# 07_Connectors_ESP32.net
KiCad netlist of a schematic drawn in Altium Designer
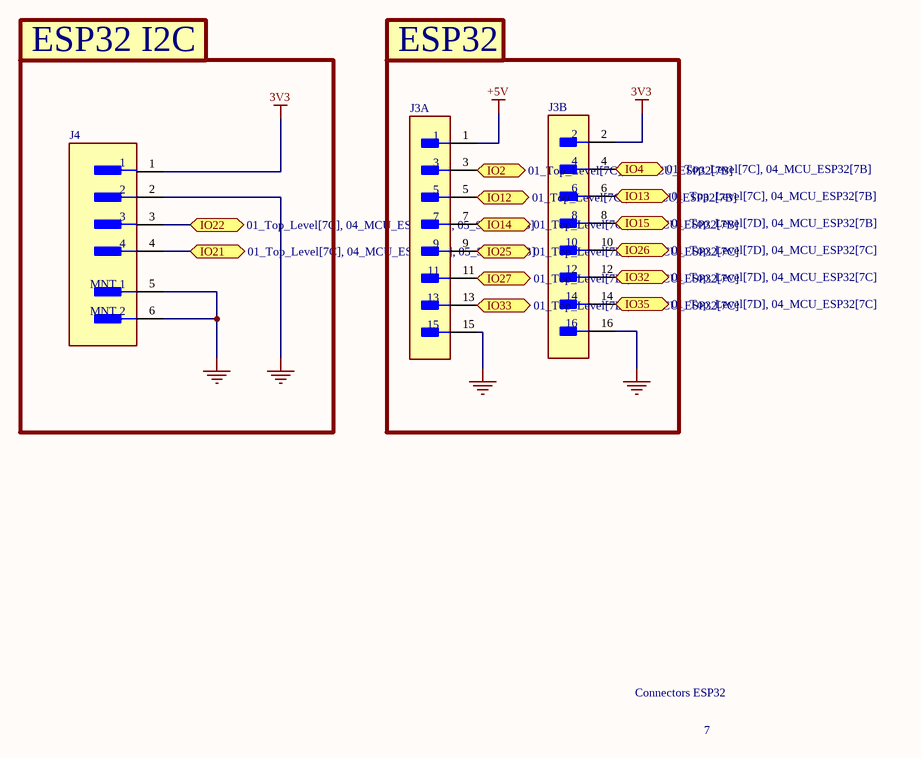
[diagram p0: 07_Connectors_ESP32.SchDoc]

(export (version "E")
  (design (tool "Eeschema 10.0.6"))
  (components
    (comp (ref "J3")
      (value "GRPB082MWCN-RC")
      (footprint "FP-GRPB082MWCN-RC-MFG")
      (description "CONN HEADER R/A 16POS 1.27MM")
      (libsource (lib "Altium Content Vault") (part "ecabc7128bd599dbeade09ffe984aba"))
    )
    (comp (ref "J4")
      (value "533980471")
      (footprint "FP-533980471-MFG")
      (description "Connector Header Surface Mount 4 position 0.049\" (1.25mm)")
      (fields (field (name "OCTOPART") "https://octopart.com/53398-0471-molex-655296"))
      (libsource (lib "Altium Content Vault") (part "3b6f738a5616415d78381ad43816e4a"))
    )
  )
  (nets
    (net (code "1") (name "+5V") (class "Default")
      (node (ref "J3") (pin "1") (pinfunction "1_1") (pintype "passive"))
    )
    (net (code "2") (name "/IO2") (class "Default")
      (node (ref "J3") (pin "3") (pinfunction "3_3") (pintype "passive"))
    )
    (net (code "3") (name "/IO4") (class "Default")
      (node (ref "J3") (pin "4") (pinfunction "4_4") (pintype "passive"))
    )
    (net (code "4") (name "/IO12") (class "Default")
      (node (ref "J3") (pin "5") (pinfunction "5_5") (pintype "passive"))
    )
    (net (code "5") (name "/IO13") (class "Default")
      (node (ref "J3") (pin "6") (pinfunction "6_6") (pintype "passive"))
    )
    (net (code "6") (name "/IO14") (class "Default")
      (node (ref "J3") (pin "7") (pinfunction "7_7") (pintype "passive"))
    )
    (net (code "7") (name "/IO15") (class "Default")
      (node (ref "J3") (pin "8") (pinfunction "8_8") (pintype "passive"))
    )
    (net (code "8") (name "/IO21") (class "Default")
      (node (ref "J4") (pin "4") (pinfunction "4_4") (pintype "passive"))
    )
    (net (code "9") (name "/IO22") (class "Default")
      (node (ref "J4") (pin "3") (pinfunction "3_3") (pintype "passive"))
    )
    (net (code "10") (name "/IO25") (class "Default")
      (node (ref "J3") (pin "9") (pinfunction "9_9") (pintype "passive"))
    )
    (net (code "11") (name "/IO26") (class "Default")
      (node (ref "J3") (pin "10") (pinfunction "10_10") (pintype "passive"))
    )
    (net (code "12") (name "/IO27") (class "Default")
      (node (ref "J3") (pin "11") (pinfunction "11_11") (pintype "passive"))
    )
    (net (code "13") (name "/IO32") (class "Default")
      (node (ref "J3") (pin "12") (pinfunction "12_12") (pintype "passive"))
    )
    (net (code "14") (name "/IO33") (class "Default")
      (node (ref "J3") (pin "13") (pinfunction "13_13") (pintype "passive"))
    )
    (net (code "15") (name "/IO35") (class "Default")
      (node (ref "J3") (pin "14") (pinfunction "14_14") (pintype "passive"))
    )
    (net (code "16") (name "3V3") (class "Default")
      (node (ref "J3") (pin "2") (pinfunction "2_2") (pintype "passive"))
      (node (ref "J4") (pin "1") (pinfunction "1_1") (pintype "passive"))
    )
    (net (code "17") (name "GND") (class "Default")
      (node (ref "J3") (pin "15") (pinfunction "15_15") (pintype "passive"))
      (node (ref "J3") (pin "16") (pinfunction "16_16") (pintype "passive"))
      (node (ref "J4") (pin "2") (pinfunction "2_2") (pintype "passive"))
      (node (ref "J4") (pin "5") (pinfunction "MNT_1_5") (pintype "passive"))
      (node (ref "J4") (pin "6") (pinfunction "MNT_2_6") (pintype "passive"))
    )
  )
)
